# top_schematic.net
KiCad netlist of a schematic drawn in EAGLE
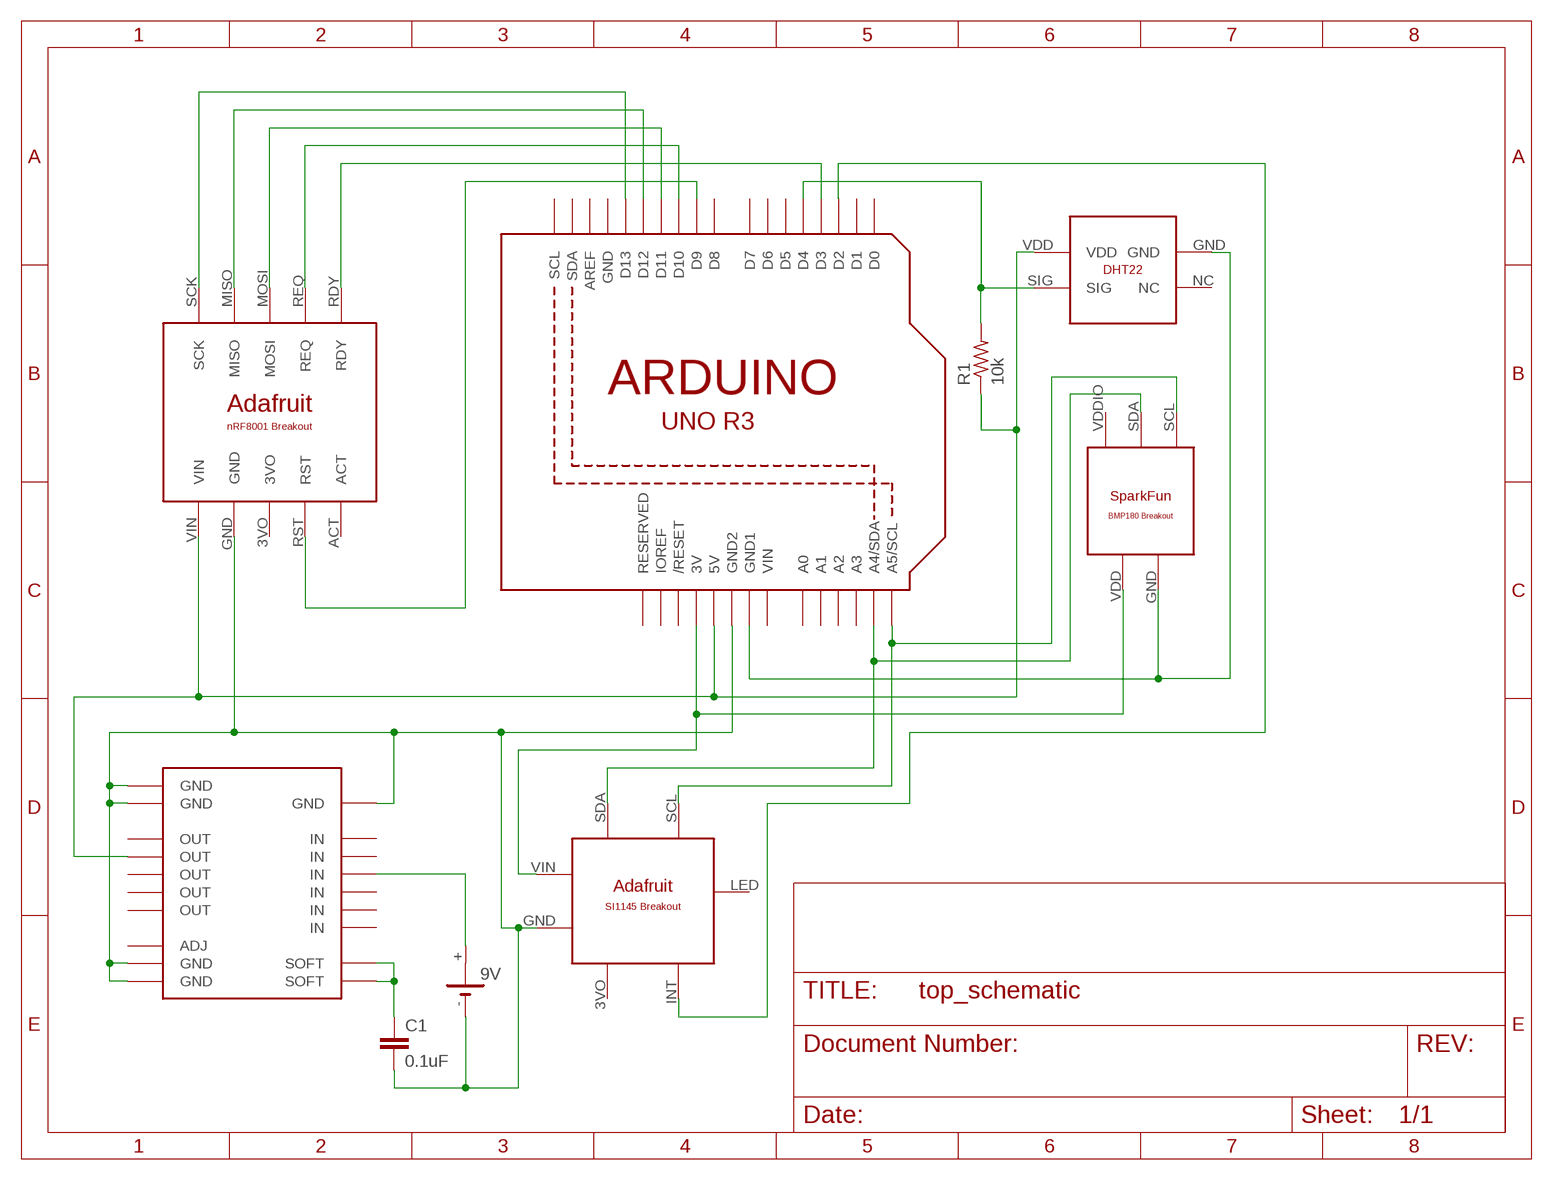
[diagram p0: schematic, sheet 1]

(export (version "E")
  (design (tool "Eeschema 10.0.6"))
  (components
    (comp (ref "9V")
      (value "1V60R")
      (footprint "eagle-import:1V60R")
      (libsource (lib "eagle-import") (part "1V60R"))
    )
    (comp (ref "C1")
      (value "0.1uF")
      (footprint "eagle-import:XC10B5")
      (libsource (lib "eagle-import") (part "CXXC10B5"))
    )
    (comp (ref "R1")
      (value "10k")
      (footprint "eagle-import:R0402")
      (libsource (lib "eagle-import") (part "R-US_R0402"))
    )
    (comp (ref "U$1")
      (value "ADAFRUIT_NRF8001_BREAKOUT")
      (footprint "eagle-import:ADAFRUIT_NRF8001_BREAKOUT_HEADERS")
      (libsource (lib "eagle-import") (part "ADAFRUIT_NRF8001_BREAKOUT"))
    )
    (comp (ref "U$2")
      (value "SPARKFUN_BMP180_BREAKOUT")
      (footprint "eagle-import:SPARKFUN_BMP180_BREAKOUT_HEADERS")
      (libsource (lib "eagle-import") (part "SPARKFUN_BMP180_BREAKOUT"))
    )
    (comp (ref "U$3")
      (value "DHT22")
      (footprint "eagle-import:DHT22_HEADERS")
      (libsource (lib "eagle-import") (part "DHT22"))
    )
    (comp (ref "U$4")
      (value "ADAFRUIT_SI1145_BREAKOUT")
      (footprint "eagle-import:ADAFRUIT_SI1145_BREAKOUT_HEADERS")
      (libsource (lib "eagle-import") (part "ADAFRUIT_SI1145_BREAKOUT"))
    )
    (comp (ref "U$5")
      (value "TI_LM2825")
      (footprint "eagle-import:TI_LM2825_HEADERS")
      (libsource (lib "eagle-import") (part "TI_LM2825"))
    )
    (comp (ref "U1")
      (value "ARDUINOR3-DIMENSION")
      (footprint "eagle-import:ARDUINOR3")
      (libsource (lib "eagle-import") (part "ARDUINOR3-DIMENSION"))
    )
  )
  (nets
    (net (code "1") (name "/3VO") (class "Default")
      (node (ref "U$4") (pin "3VO") (pinfunction "3VO_3VO") (pintype "power_in"))
    )
    (net (code "2") (name "/GND") (class "Default")
      (node (ref "U1") (pin "GND") (pinfunction "GND_GND") (pintype "power_in"))
    )
    (net (code "3") (name "/VIN") (class "Default")
      (node (ref "U1") (pin "VIN") (pinfunction "VIN_VIN") (pintype "power_in"))
    )
    (net (code "4") (name "Net-(9V-Pad+)") (class "Default")
      (node (ref "9V") (pin "+") (pinfunction "+_+") (pintype "passive"))
      (node (ref "U$5") (pin "IN@19") (pinfunction "IN_IN@19") (pintype "input"))
    )
    (net (code "5") (name "Net-(9V-Pad-)") (class "Default")
      (node (ref "9V") (pin "-") (pinfunction "-_-") (pintype "passive"))
      (node (ref "C1") (pin "2") (pinfunction "2_2") (pintype "passive"))
      (node (ref "U$1") (pin "GND") (pinfunction "GND_GND") (pintype "bidirectional"))
      (node (ref "U$4") (pin "GND") (pinfunction "GND_GND") (pintype "power_in"))
      (node (ref "U$5") (pin "GND@1") (pinfunction "GND_GND@1") (pintype "power_in"))
      (node (ref "U$5") (pin "GND@11") (pinfunction "GND_GND@11") (pintype "power_in"))
      (node (ref "U$5") (pin "GND@12") (pinfunction "GND_GND@12") (pintype "power_in"))
      (node (ref "U$5") (pin "GND@2") (pinfunction "GND_GND@2") (pintype "power_in"))
      (node (ref "U$5") (pin "GND@23") (pinfunction "GND_GND@23") (pintype "power_in"))
      (node (ref "U1") (pin "GND2") (pinfunction "GND2_GND2") (pintype "power_in"))
    )
    (net (code "6") (name "Net-(C1-Pad1)") (class "Default")
      (node (ref "C1") (pin "1") (pinfunction "1_1") (pintype "passive"))
      (node (ref "U$5") (pin "SOFT@13") (pinfunction "SOFT_SOFT@13") (pintype "passive"))
      (node (ref "U$5") (pin "SOFT@14") (pinfunction "SOFT_SOFT@14") (pintype "passive"))
    )
    (net (code "7") (name "Net-(R1-Pad1)") (class "Default")
      (node (ref "R1") (pin "1") (pinfunction "1_1") (pintype "passive"))
      (node (ref "U$1") (pin "VIN") (pinfunction "VIN_VIN") (pintype "bidirectional"))
      (node (ref "U$3") (pin "VDD") (pinfunction "VDD_VDD") (pintype "power_in"))
      (node (ref "U$5") (pin "OUT@5") (pinfunction "OUT_OUT@5") (pintype "output"))
      (node (ref "U1") (pin "5V") (pinfunction "5V_5V") (pintype "power_in"))
    )
    (net (code "8") (name "Net-(R1-Pad2)") (class "Default")
      (node (ref "R1") (pin "2") (pinfunction "2_2") (pintype "passive"))
      (node (ref "U$3") (pin "SIG") (pinfunction "SIG_SIG") (pintype "bidirectional"))
      (node (ref "U1") (pin "D4") (pinfunction "D4_D4") (pintype "bidirectional"))
    )
    (net (code "9") (name "Net-(U$1-PadMISO)") (class "Default")
      (node (ref "U$1") (pin "MISO") (pinfunction "MISO_MISO") (pintype "bidirectional"))
      (node (ref "U1") (pin "D12") (pinfunction "D12_D12") (pintype "bidirectional"))
    )
    (net (code "10") (name "Net-(U$1-PadMOSI)") (class "Default")
      (node (ref "U$1") (pin "MOSI") (pinfunction "MOSI_MOSI") (pintype "bidirectional"))
      (node (ref "U1") (pin "D11") (pinfunction "D11_D11") (pintype "bidirectional"))
    )
    (net (code "11") (name "Net-(U$1-PadRDY)") (class "Default")
      (node (ref "U$1") (pin "RDY") (pinfunction "RDY_RDY") (pintype "bidirectional"))
      (node (ref "U1") (pin "D3") (pinfunction "D3_D3") (pintype "bidirectional"))
    )
    (net (code "12") (name "Net-(U$1-PadREQ)") (class "Default")
      (node (ref "U$1") (pin "REQ") (pinfunction "REQ_REQ") (pintype "bidirectional"))
      (node (ref "U1") (pin "D10") (pinfunction "D10_D10") (pintype "bidirectional"))
    )
    (net (code "13") (name "Net-(U$1-PadRST)") (class "Default")
      (node (ref "U$1") (pin "RST") (pinfunction "RST_RST") (pintype "bidirectional"))
      (node (ref "U1") (pin "D9") (pinfunction "D9_D9") (pintype "bidirectional"))
    )
    (net (code "14") (name "Net-(U$1-PadSCK)") (class "Default")
      (node (ref "U$1") (pin "SCK") (pinfunction "SCK_SCK") (pintype "bidirectional"))
      (node (ref "U1") (pin "D13") (pinfunction "D13_D13") (pintype "bidirectional"))
    )
    (net (code "15") (name "Net-(U$2-PadGND)") (class "Default")
      (node (ref "U$2") (pin "GND") (pinfunction "GND_GND") (pintype "bidirectional"))
      (node (ref "U$3") (pin "GND") (pinfunction "GND_GND") (pintype "power_in"))
      (node (ref "U1") (pin "GND1") (pinfunction "GND1_GND1") (pintype "power_in"))
    )
    (net (code "16") (name "Net-(U$2-PadVDD)") (class "Default")
      (node (ref "U$2") (pin "VDD") (pinfunction "VDD_VDD") (pintype "bidirectional"))
      (node (ref "U$4") (pin "VIN") (pinfunction "VIN_VIN") (pintype "power_in"))
      (node (ref "U1") (pin "3V") (pinfunction "3V_3V") (pintype "power_in"))
    )
    (net (code "17") (name "Net-(U$4-PadINT)") (class "Default")
      (node (ref "U$4") (pin "INT") (pinfunction "INT_INT") (pintype "output"))
      (node (ref "U1") (pin "D2") (pinfunction "D2_D2") (pintype "bidirectional"))
    )
    (net (code "18") (name "Net-(U1-A4{slash}SDA)") (class "Default")
      (node (ref "U$2") (pin "SDA") (pinfunction "SDA_SDA") (pintype "bidirectional"))
      (node (ref "U$4") (pin "SDA") (pinfunction "SDA_SDA") (pintype "bidirectional"))
      (node (ref "U1") (pin "A4") (pinfunction "A4/SDA_A4") (pintype "bidirectional"))
    )
    (net (code "19") (name "Net-(U1-A5{slash}SCL)") (class "Default")
      (node (ref "U$2") (pin "SCL") (pinfunction "SCL_SCL") (pintype "bidirectional"))
      (node (ref "U$4") (pin "SCL") (pinfunction "SCL_SCL") (pintype "bidirectional"))
      (node (ref "U1") (pin "A5") (pinfunction "A5/SCL_A5") (pintype "bidirectional"))
    )
    (net (code "20") (name "unconnected-(9V-+-Pad+@1)") (class "Default")
      (node (ref "9V") (pin "+@1") (pinfunction "+_+@1") (pintype "passive"))
    )
    (net (code "21") (name "unconnected-(U$1-Pad3VO)") (class "Default")
      (node (ref "U$1") (pin "3VO") (pinfunction "3VO_3VO") (pintype "bidirectional"))
    )
    (net (code "22") (name "unconnected-(U$1-PadACT)") (class "Default")
      (node (ref "U$1") (pin "ACT") (pinfunction "ACT_ACT") (pintype "bidirectional"))
    )
    (net (code "23") (name "unconnected-(U$2-PadVDDIO)") (class "Default")
      (node (ref "U$2") (pin "VDDIO") (pinfunction "VDDIO_VDDIO") (pintype "bidirectional"))
    )
    (net (code "24") (name "unconnected-(U$3-PadNC)") (class "Default")
      (node (ref "U$3") (pin "NC") (pinfunction "NC_NC") (pintype "no_connect"))
    )
    (net (code "25") (name "unconnected-(U$4-PadLED)") (class "Default")
      (node (ref "U$4") (pin "LED") (pinfunction "LED_LED") (pintype "output"))
    )
    (net (code "26") (name "unconnected-(U$5-IN-PadIN@16)") (class "Default")
      (node (ref "U$5") (pin "IN@16") (pinfunction "IN_IN@16") (pintype "input"))
    )
    (net (code "27") (name "unconnected-(U$5-IN-PadIN@17)") (class "Default")
      (node (ref "U$5") (pin "IN@17") (pinfunction "IN_IN@17") (pintype "input"))
    )
    (net (code "28") (name "unconnected-(U$5-IN-PadIN@18)") (class "Default")
      (node (ref "U$5") (pin "IN@18") (pinfunction "IN_IN@18") (pintype "input"))
    )
    (net (code "29") (name "unconnected-(U$5-IN-PadIN@20)") (class "Default")
      (node (ref "U$5") (pin "IN@20") (pinfunction "IN_IN@20") (pintype "input"))
    )
    (net (code "30") (name "unconnected-(U$5-IN-PadIN@21)") (class "Default")
      (node (ref "U$5") (pin "IN@21") (pinfunction "IN_IN@21") (pintype "input"))
    )
    (net (code "31") (name "unconnected-(U$5-OUT-PadOUT@4)") (class "Default")
      (node (ref "U$5") (pin "OUT@4") (pinfunction "OUT_OUT@4") (pintype "output"))
    )
    (net (code "32") (name "unconnected-(U$5-OUT-PadOUT@6)") (class "Default")
      (node (ref "U$5") (pin "OUT@6") (pinfunction "OUT_OUT@6") (pintype "output"))
    )
    (net (code "33") (name "unconnected-(U$5-OUT-PadOUT@7)") (class "Default")
      (node (ref "U$5") (pin "OUT@7") (pinfunction "OUT_OUT@7") (pintype "output"))
    )
    (net (code "34") (name "unconnected-(U$5-OUT-PadOUT@8)") (class "Default")
      (node (ref "U$5") (pin "OUT@8") (pinfunction "OUT_OUT@8") (pintype "output"))
    )
    (net (code "35") (name "unconnected-(U$5-PadADJ)") (class "Default")
      (node (ref "U$5") (pin "ADJ") (pinfunction "ADJ_ADJ") (pintype "passive"))
    )
    (net (code "36") (name "unconnected-(U1-PadA0)") (class "Default")
      (node (ref "U1") (pin "A0") (pinfunction "A0_A0") (pintype "bidirectional"))
    )
    (net (code "37") (name "unconnected-(U1-PadA1)") (class "Default")
      (node (ref "U1") (pin "A1") (pinfunction "A1_A1") (pintype "bidirectional"))
    )
    (net (code "38") (name "unconnected-(U1-PadA2)") (class "Default")
      (node (ref "U1") (pin "A2") (pinfunction "A2_A2") (pintype "bidirectional"))
    )
    (net (code "39") (name "unconnected-(U1-PadA3)") (class "Default")
      (node (ref "U1") (pin "A3") (pinfunction "A3_A3") (pintype "bidirectional"))
    )
    (net (code "40") (name "unconnected-(U1-PadAREF)") (class "Default")
      (node (ref "U1") (pin "AREF") (pinfunction "AREF_AREF") (pintype "bidirectional"))
    )
    (net (code "41") (name "unconnected-(U1-PadD0)") (class "Default")
      (node (ref "U1") (pin "D0") (pinfunction "D0_D0") (pintype "bidirectional"))
    )
    (net (code "42") (name "unconnected-(U1-PadD1)") (class "Default")
      (node (ref "U1") (pin "D1") (pinfunction "D1_D1") (pintype "bidirectional"))
    )
    (net (code "43") (name "unconnected-(U1-PadD5)") (class "Default")
      (node (ref "U1") (pin "D5") (pinfunction "D5_D5") (pintype "bidirectional"))
    )
    (net (code "44") (name "unconnected-(U1-PadD6)") (class "Default")
      (node (ref "U1") (pin "D6") (pinfunction "D6_D6") (pintype "bidirectional"))
    )
    (net (code "45") (name "unconnected-(U1-PadD7)") (class "Default")
      (node (ref "U1") (pin "D7") (pinfunction "D7_D7") (pintype "bidirectional"))
    )
    (net (code "46") (name "unconnected-(U1-PadD8)") (class "Default")
      (node (ref "U1") (pin "D8") (pinfunction "D8_D8") (pintype "bidirectional"))
    )
    (net (code "47") (name "unconnected-(U1-PadIOREF)") (class "Default")
      (node (ref "U1") (pin "IOREF") (pinfunction "IOREF_IOREF") (pintype "output"))
    )
    (net (code "48") (name "unconnected-(U1-PadRESERVED)") (class "Default")
      (node (ref "U1") (pin "RESERVED") (pinfunction "RESERVED_RESERVED") (pintype "no_connect"))
    )
    (net (code "49") (name "unconnected-(U1-PadSCL)") (class "Default")
      (node (ref "U1") (pin "SCL") (pinfunction "SCL_SCL") (pintype "bidirectional"))
    )
    (net (code "50") (name "unconnected-(U1-PadSDA)") (class "Default")
      (node (ref "U1") (pin "SDA") (pinfunction "SDA_SDA") (pintype "bidirectional"))
    )
    (net (code "51") (name "unconnected-(U1-{slash}RESET-PadRESET)") (class "Default")
      (node (ref "U1") (pin "RESET") (pinfunction "/RESET_RESET") (pintype "bidirectional"))
    )
  )
)
